# EnergyMonitorV1_0.net
KiCad netlist of a schematic drawn in EAGLE
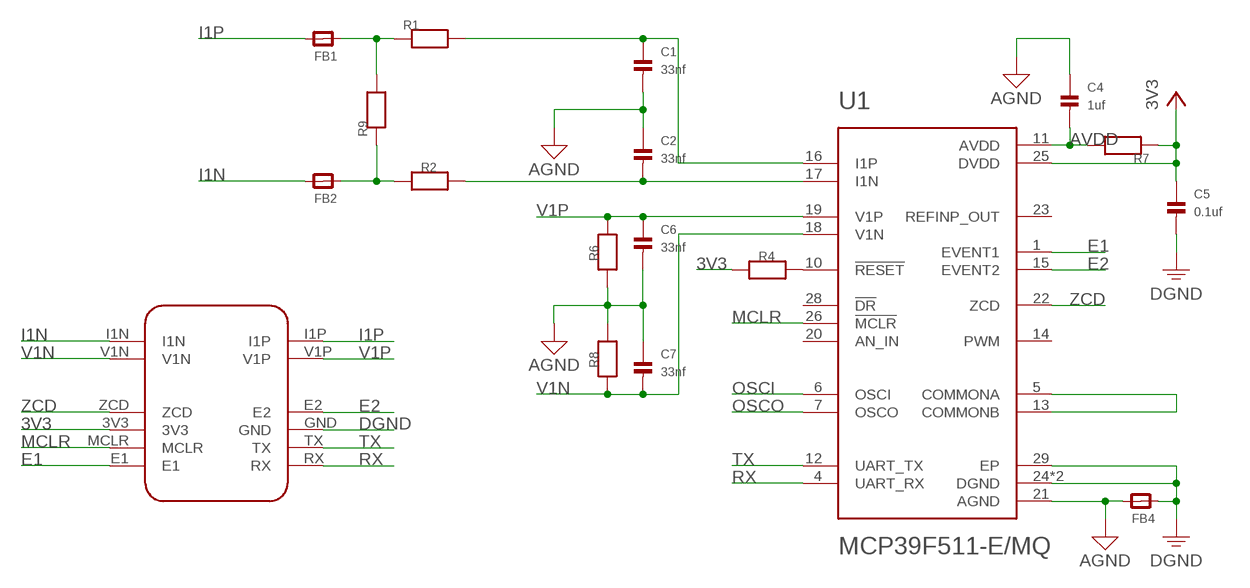
[diagram p0: schematic, sheet 1]

(export (version "E")
  (design (tool "Eeschema 10.0.6"))
  (components
    (comp (ref "C1")
      (value "33nf")
      (footprint "eagle-import:0603")
      (libsource (lib "eagle-import") (part "CAP_CERAMIC0603"))
    )
    (comp (ref "C2")
      (value "33nf")
      (footprint "eagle-import:0603")
      (libsource (lib "eagle-import") (part "CAP_CERAMIC0603"))
    )
    (comp (ref "C4")
      (value "1uf")
      (footprint "eagle-import:0603")
      (libsource (lib "eagle-import") (part "CAP_CERAMIC0603"))
    )
    (comp (ref "C5")
      (value "0.1uf")
      (footprint "eagle-import:0603")
      (libsource (lib "eagle-import") (part "CAP_CERAMIC0603"))
    )
    (comp (ref "C6")
      (value "33nf")
      (footprint "eagle-import:0603")
      (libsource (lib "eagle-import") (part "CAP_CERAMIC0603"))
    )
    (comp (ref "C7")
      (value "33nf")
      (footprint "eagle-import:0603")
      (libsource (lib "eagle-import") (part "CAP_CERAMIC0603"))
    )
    (comp (ref "FB1")
      (value "FERRITE_0603")
      (footprint "eagle-import:_0603")
      (libsource (lib "eagle-import") (part "FERRITE_0603"))
    )
    (comp (ref "FB2")
      (value "FERRITE_0603")
      (footprint "eagle-import:_0603")
      (libsource (lib "eagle-import") (part "FERRITE_0603"))
    )
    (comp (ref "FB4")
      (value "FERRITE_0603")
      (footprint "eagle-import:_0603")
      (libsource (lib "eagle-import") (part "FERRITE_0603"))
    )
    (comp (ref "R1")
      (value "1k")
      (footprint "eagle-import:0603")
      (libsource (lib "eagle-import") (part "RESISTOR0603"))
    )
    (comp (ref "R2")
      (value "1k")
      (footprint "eagle-import:0603")
      (libsource (lib "eagle-import") (part "RESISTOR0603"))
    )
    (comp (ref "R4")
      (value "10R")
      (footprint "eagle-import:0603")
      (libsource (lib "eagle-import") (part "RESISTOR0603"))
    )
    (comp (ref "R6")
      (value "1k")
      (footprint "eagle-import:0603")
      (libsource (lib "eagle-import") (part "RESISTOR0603"))
    )
    (comp (ref "R7")
      (value "10R")
      (footprint "eagle-import:0603")
      (libsource (lib "eagle-import") (part "RESISTOR0603"))
    )
    (comp (ref "R8")
      (value "1k")
      (footprint "eagle-import:0603")
      (libsource (lib "eagle-import") (part "RESISTOR0603"))
    )
    (comp (ref "R9")
      (value "2.49")
      (footprint "eagle-import:0603")
      (libsource (lib "eagle-import") (part "RESISTOR0603"))
    )
    (comp (ref "U$1")
      (value "PMIC")
      (footprint "eagle-import:PMIC")
      (libsource (lib "eagle-import") (part "PMIC"))
    )
    (comp (ref "U1")
      (value "MCP39F511-E/MQ")
      (footprint "eagle-import:QFN50P500X500X100-29N")
      (fields (field (name "DIGI-KEY_PART_NUMBER") "MCP39F511-E/MQ-ND") (field (name "MF") "Microchip"))
      (libsource (lib "eagle-import") (part "MCP39F511-E/MQ"))
    )
  )
  (nets
    (net (code "1") (name "/AVDD") (class "Default")
      (node (ref "C4") (pin "2") (pinfunction "P$2_2") (pintype "passive"))
      (node (ref "R7") (pin "2") (pinfunction "2_2") (pintype "passive"))
      (node (ref "U1") (pin "11") (pinfunction "AVDD_11") (pintype "power_in"))
    )
    (net (code "2") (name "/E1") (class "Default")
      (node (ref "U$1") (pin "E1") (pinfunction "E1_E1") (pintype "bidirectional"))
      (node (ref "U1") (pin "1") (pinfunction "EVENT1_1") (pintype "output"))
    )
    (net (code "3") (name "/E2") (class "Default")
      (node (ref "U$1") (pin "E2") (pinfunction "E2_E2") (pintype "bidirectional"))
      (node (ref "U1") (pin "15") (pinfunction "EVENT2_15") (pintype "output"))
    )
    (net (code "4") (name "/I1N") (class "Default")
      (node (ref "FB2") (pin "1") (pinfunction "P$1_1") (pintype "passive"))
      (node (ref "U$1") (pin "I1N") (pinfunction "I1N_I1N") (pintype "bidirectional"))
    )
    (net (code "5") (name "/I1P") (class "Default")
      (node (ref "FB1") (pin "1") (pinfunction "P$1_1") (pintype "passive"))
      (node (ref "U$1") (pin "I1P") (pinfunction "I1P_I1P") (pintype "bidirectional"))
    )
    (net (code "6") (name "/MCLR") (class "Default")
      (node (ref "U$1") (pin "MCLR") (pinfunction "MCLR_MCLR") (pintype "bidirectional"))
      (node (ref "U1") (pin "26") (pinfunction "~{MCLR}_26") (pintype "input"))
    )
    (net (code "7") (name "/OSCI") (class "Default")
      (node (ref "U1") (pin "6") (pinfunction "OSCI_6") (pintype "input"))
    )
    (net (code "8") (name "/OSCO") (class "Default")
      (node (ref "U1") (pin "7") (pinfunction "OSCO_7") (pintype "output"))
    )
    (net (code "9") (name "/RX") (class "Default")
      (node (ref "U$1") (pin "RX") (pinfunction "RX_RX") (pintype "bidirectional"))
      (node (ref "U1") (pin "4") (pinfunction "UART_RX_4") (pintype "bidirectional"))
    )
    (net (code "10") (name "/TX") (class "Default")
      (node (ref "U$1") (pin "TX") (pinfunction "TX_TX") (pintype "bidirectional"))
      (node (ref "U1") (pin "12") (pinfunction "UART_TX_12") (pintype "bidirectional"))
    )
    (net (code "11") (name "/V1N") (class "Default")
      (node (ref "C7") (pin "2") (pinfunction "P$2_2") (pintype "passive"))
      (node (ref "R8") (pin "1") (pinfunction "1_1") (pintype "passive"))
      (node (ref "U$1") (pin "V1N") (pinfunction "V1N_V1N") (pintype "bidirectional"))
      (node (ref "U1") (pin "18") (pinfunction "V1N_18") (pintype "input"))
    )
    (net (code "12") (name "/V1P") (class "Default")
      (node (ref "C6") (pin "1") (pinfunction "P$1_1") (pintype "passive"))
      (node (ref "R6") (pin "2") (pinfunction "2_2") (pintype "passive"))
      (node (ref "U$1") (pin "V1P") (pinfunction "V1P_V1P") (pintype "bidirectional"))
      (node (ref "U1") (pin "19") (pinfunction "V1P_19") (pintype "input"))
    )
    (net (code "13") (name "/ZCD") (class "Default")
      (node (ref "U$1") (pin "ZCD") (pinfunction "ZCD_ZCD") (pintype "bidirectional"))
      (node (ref "U1") (pin "22") (pinfunction "ZCD_22") (pintype "output"))
    )
    (net (code "14") (name "3V3") (class "Default")
      (node (ref "C5") (pin "1") (pinfunction "P$1_1") (pintype "passive"))
      (node (ref "R4") (pin "1") (pinfunction "1_1") (pintype "passive"))
      (node (ref "R7") (pin "1") (pinfunction "1_1") (pintype "passive"))
      (node (ref "U$1") (pin "3V3") (pinfunction "3V3_3V3") (pintype "bidirectional"))
      (node (ref "U1") (pin "25") (pinfunction "DVDD_25") (pintype "power_in"))
    )
    (net (code "15") (name "AGND") (class "Default")
      (node (ref "C1") (pin "2") (pinfunction "P$2_2") (pintype "passive"))
      (node (ref "C2") (pin "1") (pinfunction "P$1_1") (pintype "passive"))
      (node (ref "C4") (pin "1") (pinfunction "P$1_1") (pintype "passive"))
      (node (ref "C6") (pin "2") (pinfunction "P$2_2") (pintype "passive"))
      (node (ref "C7") (pin "1") (pinfunction "P$1_1") (pintype "passive"))
      (node (ref "FB4") (pin "1") (pinfunction "P$1_1") (pintype "passive"))
      (node (ref "R6") (pin "1") (pinfunction "1_1") (pintype "passive"))
      (node (ref "R8") (pin "2") (pinfunction "2_2") (pintype "passive"))
      (node (ref "U1") (pin "21") (pinfunction "AGND_21") (pintype "power_in"))
    )
    (net (code "16") (name "DGND") (class "Default")
      (node (ref "C5") (pin "2") (pinfunction "P$2_2") (pintype "passive"))
      (node (ref "FB4") (pin "2") (pinfunction "P$2_2") (pintype "passive"))
      (node (ref "U$1") (pin "GND") (pinfunction "GND_GND") (pintype "bidirectional"))
      (node (ref "U1") (pin "24") (pinfunction "DGND_24") (pintype "power_in"))
      (node (ref "U1") (pin "27") (pinfunction "DGND_27") (pintype "power_in"))
      (node (ref "U1") (pin "29") (pinfunction "EP_29") (pintype "power_in"))
    )
    (net (code "17") (name "Net-(C1-P$1)") (class "Default")
      (node (ref "C1") (pin "1") (pinfunction "P$1_1") (pintype "passive"))
      (node (ref "R1") (pin "2") (pinfunction "2_2") (pintype "passive"))
      (node (ref "U1") (pin "16") (pinfunction "I1P_16") (pintype "input"))
    )
    (net (code "18") (name "Net-(C2-P$2)") (class "Default")
      (node (ref "C2") (pin "2") (pinfunction "P$2_2") (pintype "passive"))
      (node (ref "R2") (pin "2") (pinfunction "2_2") (pintype "passive"))
      (node (ref "U1") (pin "17") (pinfunction "I1N_17") (pintype "input"))
    )
    (net (code "19") (name "Net-(FB1-P$2)") (class "Default")
      (node (ref "FB1") (pin "2") (pinfunction "P$2_2") (pintype "passive"))
      (node (ref "R1") (pin "1") (pinfunction "1_1") (pintype "passive"))
      (node (ref "R9") (pin "2") (pinfunction "2_2") (pintype "passive"))
    )
    (net (code "20") (name "Net-(FB2-P$2)") (class "Default")
      (node (ref "FB2") (pin "2") (pinfunction "P$2_2") (pintype "passive"))
      (node (ref "R2") (pin "1") (pinfunction "1_1") (pintype "passive"))
      (node (ref "R9") (pin "1") (pinfunction "1_1") (pintype "passive"))
    )
    (net (code "21") (name "Net-(U1-COMMONA)") (class "Default")
      (node (ref "U1") (pin "13") (pinfunction "COMMONB_13") (pintype "bidirectional"))
      (node (ref "U1") (pin "5") (pinfunction "COMMONA_5") (pintype "bidirectional"))
    )
    (net (code "22") (name "Net-(U1-~{RESET})") (class "Default")
      (node (ref "R4") (pin "2") (pinfunction "2_2") (pintype "passive"))
      (node (ref "U1") (pin "10") (pinfunction "~{RESET}_10") (pintype "input"))
    )
    (net (code "23") (name "unconnected-(U1-AN_IN-Pad20)") (class "Default")
      (node (ref "U1") (pin "20") (pinfunction "AN_IN_20") (pintype "input"))
    )
    (net (code "24") (name "unconnected-(U1-PWM-Pad14)") (class "Default")
      (node (ref "U1") (pin "14") (pinfunction "PWM_14") (pintype "output"))
    )
    (net (code "25") (name "unconnected-(U1-REFINP_OUT-Pad23)") (class "Default")
      (node (ref "U1") (pin "23") (pinfunction "REFINP_OUT_23") (pintype "output"))
    )
    (net (code "26") (name "unconnected-(U1-~{DR}-Pad28)") (class "Default")
      (node (ref "U1") (pin "28") (pinfunction "~{DR}_28") (pintype "input"))
    )
  )
)
